# napeti.net
KiCad netlist of a schematic drawn in EAGLE
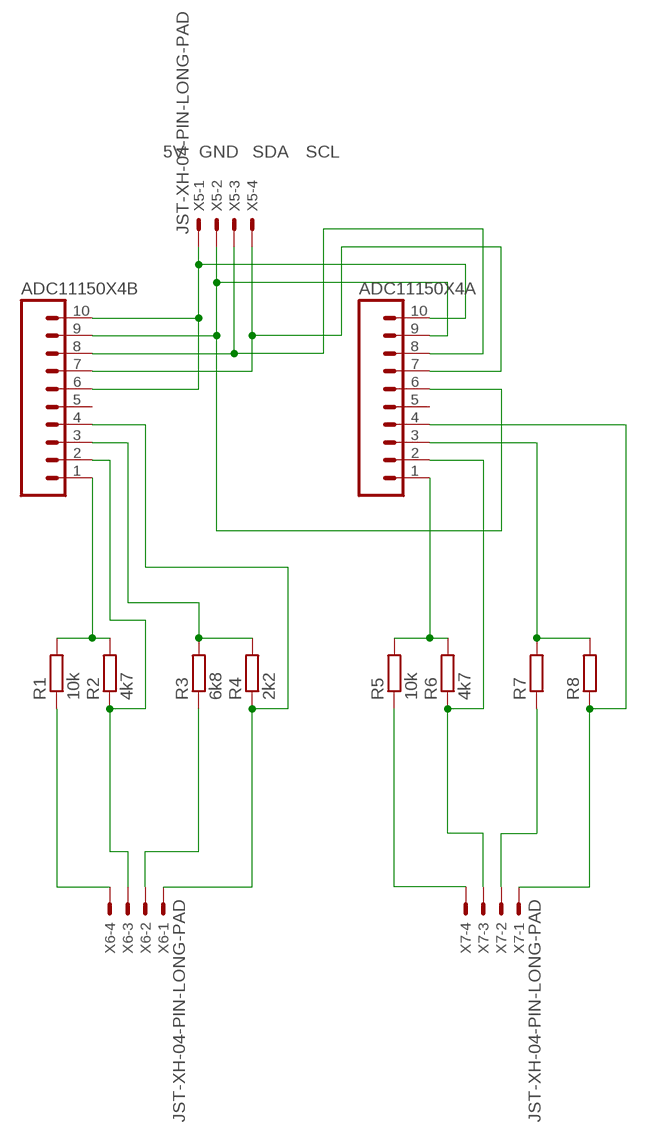
[diagram p0: schematic, sheet 1]

(export (version "E")
  (design (tool "Eeschema 10.0.6"))
  (components
    (comp (ref "ADC11150X4A")
      (value "M10")
      (footprint "eagle-import:10P")
      (libsource (lib "eagle-import") (part "M10"))
    )
    (comp (ref "ADC11150X4B")
      (value "M10")
      (footprint "eagle-import:10P")
      (libsource (lib "eagle-import") (part "M10"))
    )
    (comp (ref "R1")
      (value "10k")
      (footprint "eagle-import:0204_7")
      (libsource (lib "eagle-import") (part "R-EU_0204/7"))
    )
    (comp (ref "R2")
      (value "4k7")
      (footprint "eagle-import:0204_7")
      (libsource (lib "eagle-import") (part "R-EU_0204/7"))
    )
    (comp (ref "R3")
      (value "6k8")
      (footprint "eagle-import:0204_7")
      (libsource (lib "eagle-import") (part "R-EU_0204/7"))
    )
    (comp (ref "R4")
      (value "2k2")
      (footprint "eagle-import:0204_7")
      (libsource (lib "eagle-import") (part "R-EU_0204/7"))
    )
    (comp (ref "R5")
      (value "10k")
      (footprint "eagle-import:0204_7")
      (libsource (lib "eagle-import") (part "R-EU_0204/7"))
    )
    (comp (ref "R6")
      (value "4k7")
      (footprint "eagle-import:0204_7")
      (libsource (lib "eagle-import") (part "R-EU_0204/7"))
    )
    (comp (ref "R7")
      (value "R-EU_0204/7")
      (footprint "eagle-import:0204_7")
      (libsource (lib "eagle-import") (part "R-EU_0204/7"))
    )
    (comp (ref "R8")
      (value "R-EU_0204/7")
      (footprint "eagle-import:0204_7")
      (libsource (lib "eagle-import") (part "R-EU_0204/7"))
    )
    (comp (ref "X5")
      (value "JST-XH-04-PIN-LONG-PAD")
      (footprint "eagle-import:JST-XH-04-PACKAGE-LONG-PAD")
      (libsource (lib "eagle-import") (part "JST-XH-04-PIN-LONG-PAD"))
    )
    (comp (ref "X6")
      (value "JST-XH-04-PIN-LONG-PAD")
      (footprint "eagle-import:JST-XH-04-PACKAGE-LONG-PAD")
      (libsource (lib "eagle-import") (part "JST-XH-04-PIN-LONG-PAD"))
    )
    (comp (ref "X7")
      (value "JST-XH-04-PIN-LONG-PAD")
      (footprint "eagle-import:JST-XH-04-PACKAGE-LONG-PAD")
      (libsource (lib "eagle-import") (part "JST-XH-04-PIN-LONG-PAD"))
    )
  )
  (nets
    (net (code "1") (name "/5V") (class "Default")
      (node (ref "ADC11150X4A") (pin "10") (pinfunction "10_10") (pintype "passive"))
      (node (ref "ADC11150X4B") (pin "10") (pinfunction "10_10") (pintype "passive"))
      (node (ref "ADC11150X4B") (pin "6") (pinfunction "6_6") (pintype "passive"))
      (node (ref "X5") (pin "1") (pinfunction "S_1") (pintype "passive"))
    )
    (net (code "2") (name "/GND") (class "Default")
      (node (ref "ADC11150X4A") (pin "6") (pinfunction "6_6") (pintype "passive"))
      (node (ref "ADC11150X4A") (pin "9") (pinfunction "9_9") (pintype "passive"))
      (node (ref "ADC11150X4B") (pin "9") (pinfunction "9_9") (pintype "passive"))
      (node (ref "X5") (pin "2") (pinfunction "S_2") (pintype "passive"))
    )
    (net (code "3") (name "/SCL") (class "Default")
      (node (ref "ADC11150X4A") (pin "7") (pinfunction "7_7") (pintype "passive"))
      (node (ref "ADC11150X4B") (pin "7") (pinfunction "7_7") (pintype "passive"))
      (node (ref "X5") (pin "4") (pinfunction "S_4") (pintype "passive"))
    )
    (net (code "4") (name "/SDA") (class "Default")
      (node (ref "ADC11150X4A") (pin "8") (pinfunction "8_8") (pintype "passive"))
      (node (ref "ADC11150X4B") (pin "8") (pinfunction "8_8") (pintype "passive"))
      (node (ref "X5") (pin "3") (pinfunction "S_3") (pintype "passive"))
    )
    (net (code "5") (name "Net-(ADC11150X4A-Pad1)") (class "Default")
      (node (ref "ADC11150X4A") (pin "1") (pinfunction "1_1") (pintype "passive"))
      (node (ref "R5") (pin "2") (pinfunction "2_2") (pintype "passive"))
      (node (ref "R6") (pin "2") (pinfunction "2_2") (pintype "passive"))
    )
    (net (code "6") (name "Net-(ADC11150X4A-Pad3)") (class "Default")
      (node (ref "ADC11150X4A") (pin "3") (pinfunction "3_3") (pintype "passive"))
      (node (ref "R7") (pin "2") (pinfunction "2_2") (pintype "passive"))
      (node (ref "R8") (pin "2") (pinfunction "2_2") (pintype "passive"))
    )
    (net (code "7") (name "Net-(ADC11150X4B-Pad1)") (class "Default")
      (node (ref "ADC11150X4B") (pin "1") (pinfunction "1_1") (pintype "passive"))
      (node (ref "R1") (pin "2") (pinfunction "2_2") (pintype "passive"))
      (node (ref "R2") (pin "2") (pinfunction "2_2") (pintype "passive"))
    )
    (net (code "8") (name "Net-(ADC11150X4B-Pad3)") (class "Default")
      (node (ref "ADC11150X4B") (pin "3") (pinfunction "3_3") (pintype "passive"))
      (node (ref "R3") (pin "2") (pinfunction "2_2") (pintype "passive"))
      (node (ref "R4") (pin "2") (pinfunction "2_2") (pintype "passive"))
    )
    (net (code "9") (name "Net-(X6A-S)") (class "Default")
      (node (ref "ADC11150X4B") (pin "4") (pinfunction "4_4") (pintype "passive"))
      (node (ref "R4") (pin "1") (pinfunction "1_1") (pintype "passive"))
      (node (ref "X6") (pin "1") (pinfunction "S_1") (pintype "passive"))
    )
    (net (code "10") (name "Net-(X6B-S)") (class "Default")
      (node (ref "R3") (pin "1") (pinfunction "1_1") (pintype "passive"))
      (node (ref "X6") (pin "2") (pinfunction "S_2") (pintype "passive"))
    )
    (net (code "11") (name "Net-(X6C-S)") (class "Default")
      (node (ref "ADC11150X4B") (pin "2") (pinfunction "2_2") (pintype "passive"))
      (node (ref "R2") (pin "1") (pinfunction "1_1") (pintype "passive"))
      (node (ref "X6") (pin "3") (pinfunction "S_3") (pintype "passive"))
    )
    (net (code "12") (name "Net-(X6D-S)") (class "Default")
      (node (ref "R1") (pin "1") (pinfunction "1_1") (pintype "passive"))
      (node (ref "X6") (pin "4") (pinfunction "S_4") (pintype "passive"))
    )
    (net (code "13") (name "Net-(X7A-S)") (class "Default")
      (node (ref "ADC11150X4A") (pin "4") (pinfunction "4_4") (pintype "passive"))
      (node (ref "R8") (pin "1") (pinfunction "1_1") (pintype "passive"))
      (node (ref "X7") (pin "1") (pinfunction "S_1") (pintype "passive"))
    )
    (net (code "14") (name "Net-(X7B-S)") (class "Default")
      (node (ref "R7") (pin "1") (pinfunction "1_1") (pintype "passive"))
      (node (ref "X7") (pin "2") (pinfunction "S_2") (pintype "passive"))
    )
    (net (code "15") (name "Net-(X7C-S)") (class "Default")
      (node (ref "ADC11150X4A") (pin "2") (pinfunction "2_2") (pintype "passive"))
      (node (ref "R6") (pin "1") (pinfunction "1_1") (pintype "passive"))
      (node (ref "X7") (pin "3") (pinfunction "S_3") (pintype "passive"))
    )
    (net (code "16") (name "Net-(X7D-S)") (class "Default")
      (node (ref "R5") (pin "1") (pinfunction "1_1") (pintype "passive"))
      (node (ref "X7") (pin "4") (pinfunction "S_4") (pintype "passive"))
    )
    (net (code "17") (name "unconnected-(ADC11150X4A-Pad5)") (class "Default")
      (node (ref "ADC11150X4A") (pin "5") (pinfunction "5_5") (pintype "passive"))
    )
    (net (code "18") (name "unconnected-(ADC11150X4B-Pad5)") (class "Default")
      (node (ref "ADC11150X4B") (pin "5") (pinfunction "5_5") (pintype "passive"))
    )
  )
)
